# tracker.net
KiCad netlist of a schematic drawn in EAGLE
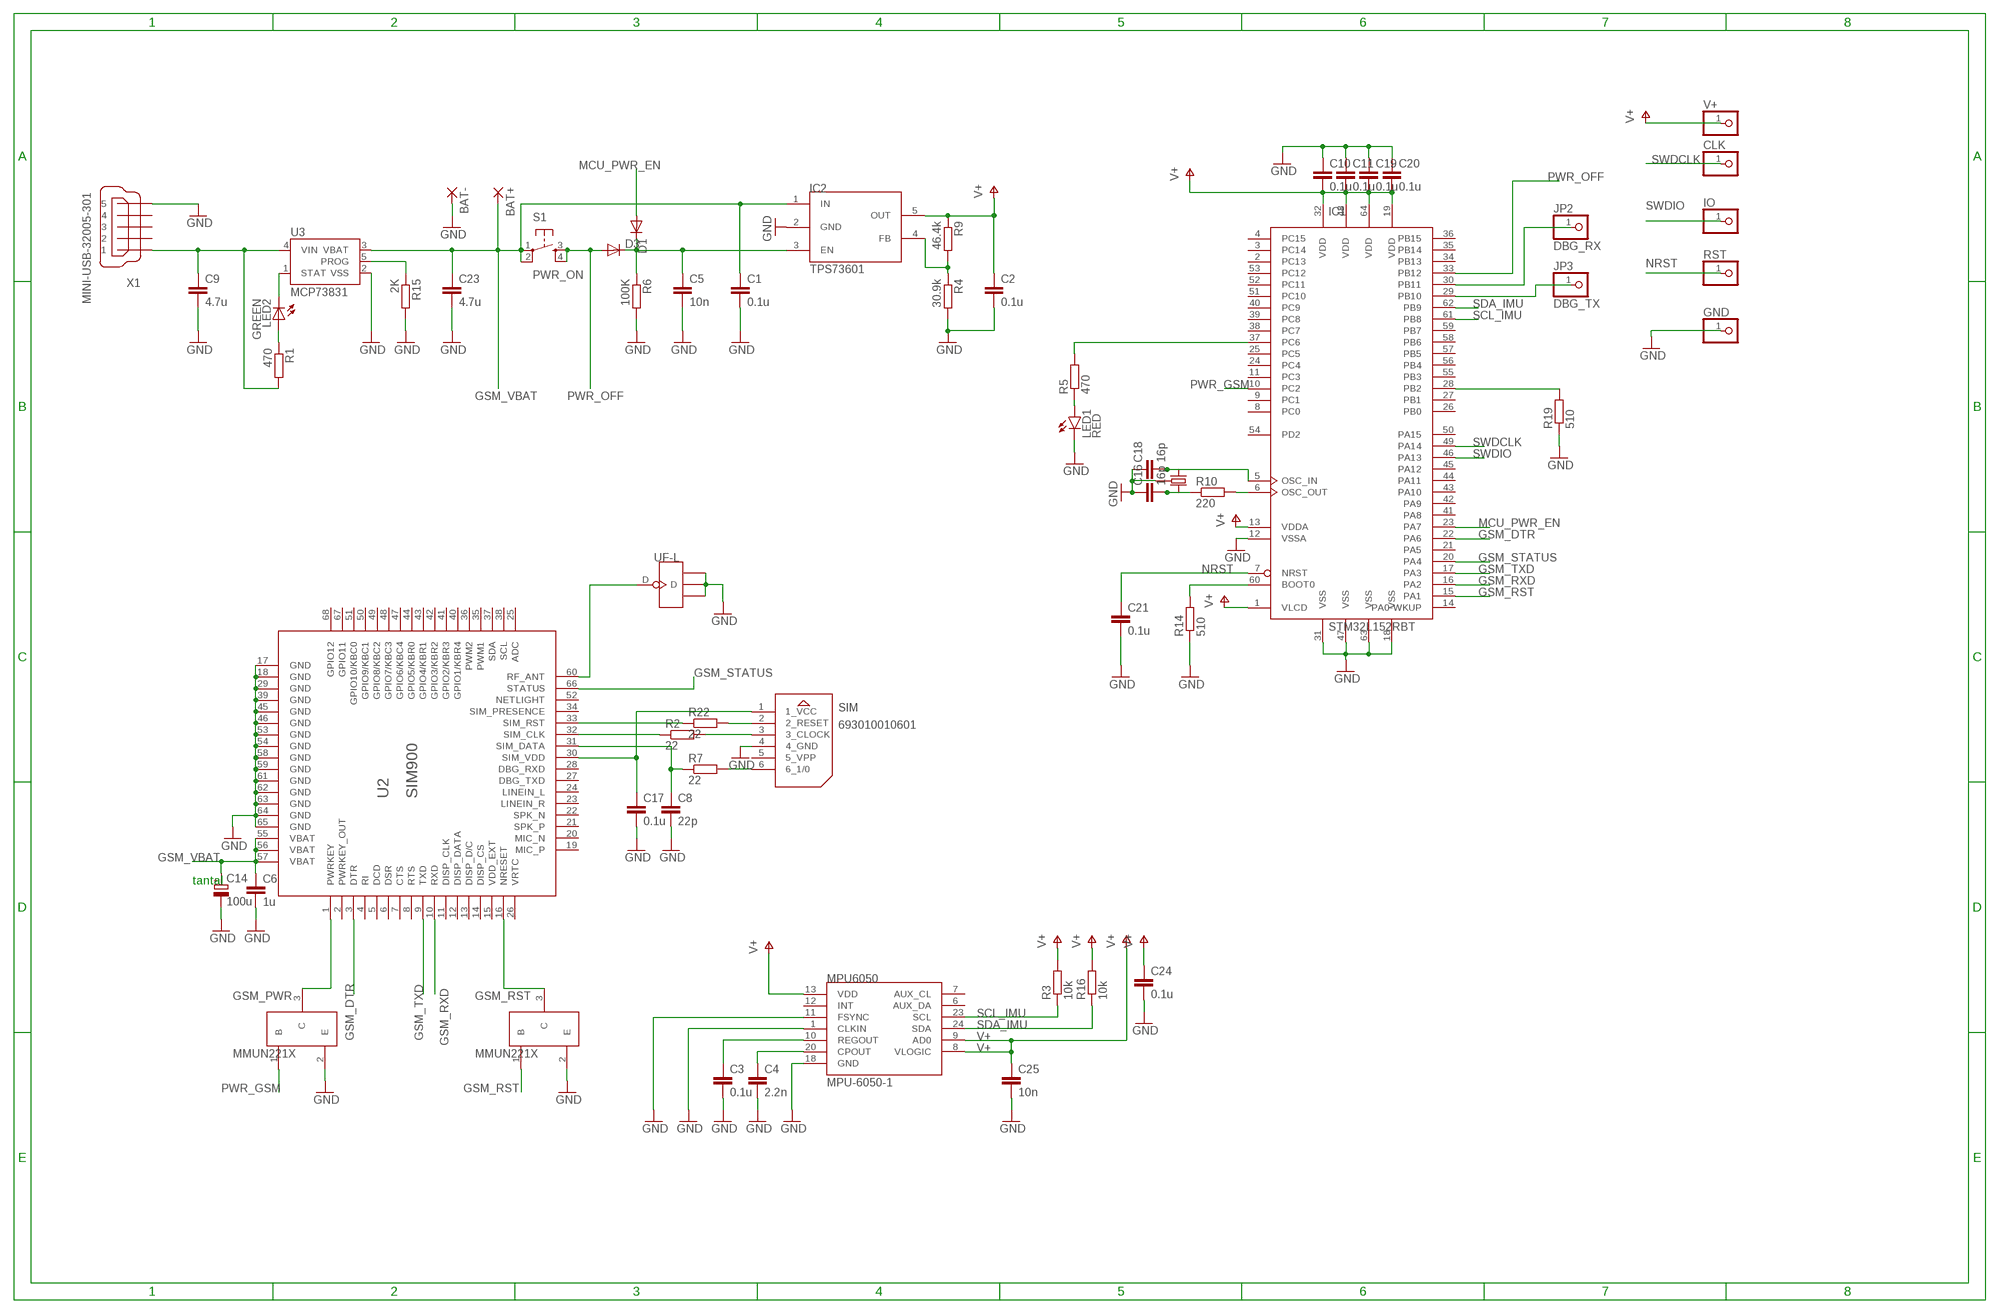
[diagram p0: schematic, sheet 1]

(export (version "E")
  (design (tool "Eeschema 10.0.6"))
  (components
    (comp (ref "BAT+")
      (value "SMD2")
      (footprint "eagle-import:SMD1,27-2,54")
      (libsource (lib "eagle-import") (part "SMD2"))
    )
    (comp (ref "BAT-")
      (value "SMD2")
      (footprint "eagle-import:SMD1,27-2,54")
      (libsource (lib "eagle-import") (part "SMD2"))
    )
    (comp (ref "C1")
      (value "0.1u")
      (footprint "eagle-import:C0805")
      (libsource (lib "eagle-import") (part "C-EUC0805"))
    )
    (comp (ref "C2")
      (value "0.1u")
      (footprint "eagle-import:C0805")
      (libsource (lib "eagle-import") (part "C-EUC0805"))
    )
    (comp (ref "C3")
      (value "0.1u")
      (footprint "eagle-import:C0805")
      (libsource (lib "eagle-import") (part "C-EUC0805"))
    )
    (comp (ref "C4")
      (value "2.2n")
      (footprint "eagle-import:C0805")
      (libsource (lib "eagle-import") (part "C-EUC0805"))
    )
    (comp (ref "C5")
      (value "10n")
      (footprint "eagle-import:C0805")
      (libsource (lib "eagle-import") (part "C-EUC0805"))
    )
    (comp (ref "C6")
      (value "1u")
      (footprint "eagle-import:C0805")
      (libsource (lib "eagle-import") (part "C-EUC0805"))
    )
    (comp (ref "C8")
      (value "22p")
      (footprint "eagle-import:C0805")
      (libsource (lib "eagle-import") (part "C-EUC0805"))
    )
    (comp (ref "C9")
      (value "4.7u")
      (footprint "eagle-import:C0805")
      (libsource (lib "eagle-import") (part "C-EUC0805"))
    )
    (comp (ref "C10")
      (value "0.1u")
      (footprint "eagle-import:C0805")
      (libsource (lib "eagle-import") (part "C-EUC0805"))
    )
    (comp (ref "C11")
      (value "0.1u")
      (footprint "eagle-import:C0805")
      (libsource (lib "eagle-import") (part "C-EUC0805"))
    )
    (comp (ref "C14")
      (value "100u")
      (footprint "eagle-import:C_6032-28R")
      (libsource (lib "eagle-import") (part "CPOL-EUC/6032-28R"))
    )
    (comp (ref "C16")
      (value "16p")
      (footprint "eagle-import:C0603")
      (libsource (lib "eagle-import") (part "C-EUC0603"))
    )
    (comp (ref "C17")
      (value "0.1u")
      (footprint "eagle-import:C0805")
      (libsource (lib "eagle-import") (part "C-EUC0805"))
    )
    (comp (ref "C18")
      (value "16p")
      (footprint "eagle-import:C0603")
      (libsource (lib "eagle-import") (part "C-EUC0603"))
    )
    (comp (ref "C19")
      (value "0.1u")
      (footprint "eagle-import:C0805")
      (libsource (lib "eagle-import") (part "C-EUC0805"))
    )
    (comp (ref "C20")
      (value "0.1u")
      (footprint "eagle-import:C0805")
      (libsource (lib "eagle-import") (part "C-EUC0805"))
    )
    (comp (ref "C21")
      (value "0.1u")
      (footprint "eagle-import:C0805")
      (libsource (lib "eagle-import") (part "C-EUC0805"))
    )
    (comp (ref "C23")
      (value "4.7u")
      (footprint "eagle-import:C0805")
      (libsource (lib "eagle-import") (part "C-EUC0805"))
    )
    (comp (ref "C24")
      (value "0.1u")
      (footprint "eagle-import:C0805")
      (libsource (lib "eagle-import") (part "C-EUC0805"))
    )
    (comp (ref "C25")
      (value "10n")
      (footprint "eagle-import:C0805")
      (libsource (lib "eagle-import") (part "C-EUC0805"))
    )
    (comp (ref "CLK")
      (value "PINHD-1X1")
      (footprint "eagle-import:1X01")
      (libsource (lib "eagle-import") (part "PINHD-1X1"))
    )
    (comp (ref "CRTL")
      (value "CRYSTAL-GROUNDED")
      (footprint "eagle-import:CRYSTAL-SMD-5X3")
      (libsource (lib "eagle-import") (part "CRYSTAL-GROUNDED"))
    )
    (comp (ref "D1")
      (value "MBR0520LT")
      (footprint "eagle-import:SOD123")
      (libsource (lib "eagle-import") (part "MBR0520LT"))
    )
    (comp (ref "D3")
      (value "MBR0520LT")
      (footprint "eagle-import:SOD123")
      (libsource (lib "eagle-import") (part "MBR0520LT"))
    )
    (comp (ref "GND")
      (value "PINHD-1X1")
      (footprint "eagle-import:1X01")
      (libsource (lib "eagle-import") (part "PINHD-1X1"))
    )
    (comp (ref "GSM_PWR")
      (value "MMUN221X")
      (footprint "eagle-import:MMUN221X")
      (libsource (lib "eagle-import") (part "MMUN221X"))
    )
    (comp (ref "GSM_RST")
      (value "MMUN221X")
      (footprint "eagle-import:MMUN221X")
      (libsource (lib "eagle-import") (part "MMUN221X"))
    )
    (comp (ref "IC1")
      (value "STM32L152RBT")
      (footprint "eagle-import:LQFP64")
      (fields (field (name "OC_NEWARK") "unknown"))
      (libsource (lib "eagle-import") (part "STM32L152RTB"))
    )
    (comp (ref "IC2")
      (value "TPS73601")
      (footprint "eagle-import:SOT23")
      (libsource (lib "eagle-import") (part "TPS73601"))
    )
    (comp (ref "IO")
      (value "PINHD-1X1")
      (footprint "eagle-import:1X01")
      (libsource (lib "eagle-import") (part "PINHD-1X1"))
    )
    (comp (ref "JP2")
      (value "DBG_RX")
      (footprint "eagle-import:1X01")
      (libsource (lib "eagle-import") (part "PINHD-1X1"))
    )
    (comp (ref "JP3")
      (value "DBG_TX")
      (footprint "eagle-import:1X01")
      (libsource (lib "eagle-import") (part "PINHD-1X1"))
    )
    (comp (ref "LED1")
      (value "RED")
      (footprint "eagle-import:LED-0603")
      (libsource (lib "eagle-import") (part "LED-RED0603"))
    )
    (comp (ref "LED2")
      (value "GREEN")
      (footprint "eagle-import:LED-0603")
      (libsource (lib "eagle-import") (part "LED0603"))
    )
    (comp (ref "MPU6050")
      (value "MPU-6050-1")
      (footprint "eagle-import:QFN-24-4MM2")
      (libsource (lib "eagle-import") (part "MPU-6050-1"))
    )
    (comp (ref "R1")
      (value "470")
      (footprint "eagle-import:R0805")
      (libsource (lib "eagle-import") (part "R-EU_R0805"))
    )
    (comp (ref "R2")
      (value "22")
      (footprint "eagle-import:R0805")
      (libsource (lib "eagle-import") (part "R-EU_R0805"))
    )
    (comp (ref "R3")
      (value "10k")
      (footprint "eagle-import:R0805")
      (libsource (lib "eagle-import") (part "R-EU_R0805"))
    )
    (comp (ref "R4")
      (value "30.9k")
      (footprint "eagle-import:R0805")
      (libsource (lib "eagle-import") (part "R-EU_R0805"))
    )
    (comp (ref "R5")
      (value "470")
      (footprint "eagle-import:R0805")
      (libsource (lib "eagle-import") (part "R-EU_R0805"))
    )
    (comp (ref "R6")
      (value "100K")
      (footprint "eagle-import:R0805")
      (libsource (lib "eagle-import") (part "R-EU_R0805"))
    )
    (comp (ref "R7")
      (value "22")
      (footprint "eagle-import:R0805")
      (libsource (lib "eagle-import") (part "R-EU_R0805"))
    )
    (comp (ref "R9")
      (value "46.4k")
      (footprint "eagle-import:R0805")
      (libsource (lib "eagle-import") (part "R-EU_R0805"))
    )
    (comp (ref "R10")
      (value "220")
      (footprint "eagle-import:R0805")
      (libsource (lib "eagle-import") (part "R-EU_R0805"))
    )
    (comp (ref "R14")
      (value "510")
      (footprint "eagle-import:R0805")
      (libsource (lib "eagle-import") (part "R-EU_R0805"))
    )
    (comp (ref "R15")
      (value "2K")
      (footprint "eagle-import:R0805")
      (libsource (lib "eagle-import") (part "R-EU_R0805"))
    )
    (comp (ref "R16")
      (value "10k")
      (footprint "eagle-import:R0805")
      (libsource (lib "eagle-import") (part "R-EU_R0805"))
    )
    (comp (ref "R19")
      (value "510")
      (footprint "eagle-import:R0805")
      (libsource (lib "eagle-import") (part "R-EU_R0805"))
    )
    (comp (ref "R22")
      (value "22")
      (footprint "eagle-import:R0805")
      (libsource (lib "eagle-import") (part "R-EU_R0805"))
    )
    (comp (ref "RST")
      (value "PINHD-1X1")
      (footprint "eagle-import:1X01")
      (libsource (lib "eagle-import") (part "PINHD-1X1"))
    )
    (comp (ref "S1")
      (value "PWR_ON")
      (footprint "eagle-import:TACTILE-PTH")
      (libsource (lib "eagle-import") (part "TAC_SWITCHPTH"))
    )
    (comp (ref "SIM")
      (value "693010010601")
      (footprint "eagle-import:693010010601")
      (libsource (lib "eagle-import") (part "693010010601"))
    )
    (comp (ref "U2")
      (value "SIM900")
      (footprint "eagle-import:SIM900")
      (libsource (lib "eagle-import") (part "SIM900"))
    )
    (comp (ref "U3")
      (value "MCP73831")
      (footprint "eagle-import:SOT23-5")
      (libsource (lib "eagle-import") (part "MCP73831"))
    )
    (comp (ref "UF-L")
      (value "ANTENNA-U-FL")
      (footprint "eagle-import:4P-U-FL")
      (libsource (lib "eagle-import") (part "ANTENNA-U-FL"))
    )
    (comp (ref "V+")
      (value "PINHD-1X1")
      (footprint "eagle-import:1X01")
      (libsource (lib "eagle-import") (part "PINHD-1X1"))
    )
    (comp (ref "X1")
      (value "MINI-USB-32005-301")
      (footprint "eagle-import:32005-301")
      (libsource (lib "eagle-import") (part "MINI-USB-32005-301"))
    )
  )
  (nets
    (net (code "1") (name "/GSM_DTR") (class "Default")
      (node (ref "IC1") (pin "22") (pinfunction "PA6_22") (pintype "bidirectional"))
      (node (ref "U2") (pin "3") (pinfunction "DTR_3") (pintype "input"))
    )
    (net (code "2") (name "/GSM_RST") (class "Default")
      (node (ref "GSM_RST") (pin "1") (pinfunction "B_1") (pintype "bidirectional"))
      (node (ref "IC1") (pin "15") (pinfunction "PA1_15") (pintype "bidirectional"))
    )
    (net (code "3") (name "/GSM_RXD") (class "Default")
      (node (ref "IC1") (pin "16") (pinfunction "PA2_16") (pintype "bidirectional"))
      (node (ref "U2") (pin "10") (pinfunction "RXD_10") (pintype "input"))
    )
    (net (code "4") (name "/GSM_STATUS") (class "Default")
      (node (ref "IC1") (pin "20") (pinfunction "PA4_20") (pintype "bidirectional"))
      (node (ref "U2") (pin "66") (pinfunction "STATUS_66") (pintype "output"))
    )
    (net (code "5") (name "/GSM_TXD") (class "Default")
      (node (ref "IC1") (pin "17") (pinfunction "PA3_17") (pintype "bidirectional"))
      (node (ref "U2") (pin "9") (pinfunction "TXD_9") (pintype "output"))
    )
    (net (code "6") (name "/GSM_VBAT") (class "Default")
      (node (ref "BAT+") (pin "1") (pinfunction "P_1") (pintype "passive"))
      (node (ref "C1") (pin "1") (pinfunction "1_1") (pintype "passive"))
      (node (ref "C14") (pin "+") (pinfunction "+_+") (pintype "passive"))
      (node (ref "C23") (pin "1") (pinfunction "1_1") (pintype "passive"))
      (node (ref "C6") (pin "1") (pinfunction "1_1") (pintype "passive"))
      (node (ref "IC2") (pin "1") (pinfunction "IN_1") (pintype "power_in"))
      (node (ref "S1") (pin "1") (pinfunction "1_1") (pintype "passive"))
      (node (ref "S1") (pin "2") (pinfunction "2_2") (pintype "passive"))
      (node (ref "U2") (pin "55") (pinfunction "VBAT_55") (pintype "power_in"))
      (node (ref "U2") (pin "56") (pinfunction "VBAT_56") (pintype "power_in"))
      (node (ref "U2") (pin "57") (pinfunction "VBAT_57") (pintype "power_in"))
      (node (ref "U3") (pin "3") (pinfunction "VBAT_3") (pintype "power_in"))
    )
    (net (code "7") (name "/MCU_PWR_EN") (class "Default")
      (node (ref "D1") (pin "A") (pinfunction "A_A") (pintype "passive"))
      (node (ref "IC1") (pin "23") (pinfunction "PA7_23") (pintype "bidirectional"))
    )
    (net (code "8") (name "/NRST") (class "Default")
      (node (ref "C21") (pin "1") (pinfunction "1_1") (pintype "passive"))
      (node (ref "IC1") (pin "7") (pinfunction "NRST_7") (pintype "bidirectional"))
      (node (ref "RST") (pin "1") (pinfunction "1_1") (pintype "passive"))
    )
    (net (code "9") (name "/PWR_GSM") (class "Default")
      (node (ref "GSM_PWR") (pin "1") (pinfunction "B_1") (pintype "bidirectional"))
      (node (ref "IC1") (pin "10") (pinfunction "PC2_10") (pintype "bidirectional"))
    )
    (net (code "10") (name "/PWR_OFF") (class "Default")
      (node (ref "D3") (pin "A") (pinfunction "A_A") (pintype "passive"))
      (node (ref "IC1") (pin "33") (pinfunction "PB12_33") (pintype "bidirectional"))
      (node (ref "S1") (pin "3") (pinfunction "3_3") (pintype "passive"))
      (node (ref "S1") (pin "4") (pinfunction "4_4") (pintype "passive"))
    )
    (net (code "11") (name "/SCL_IMU") (class "Default")
      (node (ref "IC1") (pin "61") (pinfunction "PB8_61") (pintype "bidirectional"))
      (node (ref "MPU6050") (pin "23") (pinfunction "SCL_23") (pintype "bidirectional"))
      (node (ref "R3") (pin "1") (pinfunction "1_1") (pintype "passive"))
    )
    (net (code "12") (name "/SDA_IMU") (class "Default")
      (node (ref "IC1") (pin "62") (pinfunction "PB9_62") (pintype "bidirectional"))
      (node (ref "MPU6050") (pin "24") (pinfunction "SDA_24") (pintype "bidirectional"))
      (node (ref "R16") (pin "1") (pinfunction "1_1") (pintype "passive"))
    )
    (net (code "13") (name "/SWDCLK") (class "Default")
      (node (ref "CLK") (pin "1") (pinfunction "1_1") (pintype "passive"))
      (node (ref "IC1") (pin "49") (pinfunction "PA14_49") (pintype "bidirectional"))
    )
    (net (code "14") (name "/SWDIO") (class "Default")
      (node (ref "IC1") (pin "46") (pinfunction "PA13_46") (pintype "bidirectional"))
      (node (ref "IO") (pin "1") (pinfunction "1_1") (pintype "passive"))
    )
    (net (code "15") (name "GND") (class "Default")
      (node (ref "BAT-") (pin "1") (pinfunction "P_1") (pintype "passive"))
      (node (ref "C1") (pin "2") (pinfunction "2_2") (pintype "passive"))
      (node (ref "C10") (pin "1") (pinfunction "1_1") (pintype "passive"))
      (node (ref "C11") (pin "1") (pinfunction "1_1") (pintype "passive"))
      (node (ref "C14") (pin "-") (pinfunction "-_-") (pintype "passive"))
      (node (ref "C16") (pin "1") (pinfunction "1_1") (pintype "passive"))
      (node (ref "C17") (pin "2") (pinfunction "2_2") (pintype "passive"))
      (node (ref "C18") (pin "1") (pinfunction "1_1") (pintype "passive"))
      (node (ref "C19") (pin "1") (pinfunction "1_1") (pintype "passive"))
      (node (ref "C2") (pin "2") (pinfunction "2_2") (pintype "passive"))
      (node (ref "C20") (pin "1") (pinfunction "1_1") (pintype "passive"))
      (node (ref "C21") (pin "2") (pinfunction "2_2") (pintype "passive"))
      (node (ref "C23") (pin "2") (pinfunction "2_2") (pintype "passive"))
      (node (ref "C24") (pin "2") (pinfunction "2_2") (pintype "passive"))
      (node (ref "C25") (pin "2") (pinfunction "2_2") (pintype "passive"))
      (node (ref "C3") (pin "2") (pinfunction "2_2") (pintype "passive"))
      (node (ref "C4") (pin "2") (pinfunction "2_2") (pintype "passive"))
      (node (ref "C5") (pin "2") (pinfunction "2_2") (pintype "passive"))
      (node (ref "C6") (pin "2") (pinfunction "2_2") (pintype "passive"))
      (node (ref "C8") (pin "2") (pinfunction "2_2") (pintype "passive"))
      (node (ref "C9") (pin "2") (pinfunction "2_2") (pintype "passive"))
      (node (ref "CRTL") (pin "2") (pinfunction "3_2") (pintype "passive"))
      (node (ref "CRTL") (pin "4") (pinfunction "3_4") (pintype "passive"))
      (node (ref "GND") (pin "1") (pinfunction "1_1") (pintype "passive"))
      (node (ref "GSM_PWR") (pin "2") (pinfunction "E_2") (pintype "bidirectional"))
      (node (ref "GSM_RST") (pin "2") (pinfunction "E_2") (pintype "bidirectional"))
      (node (ref "IC1") (pin "12") (pinfunction "VSSA_12") (pintype "power_in"))
      (node (ref "IC1") (pin "18") (pinfunction "VSS_18") (pintype "power_in"))
      (node (ref "IC1") (pin "31") (pinfunction "VSS_31") (pintype "power_in"))
      (node (ref "IC1") (pin "47") (pinfunction "VSS_47") (pintype "power_in"))
      (node (ref "IC1") (pin "63") (pinfunction "VSS_63") (pintype "power_in"))
      (node (ref "IC2") (pin "2") (pinfunction "GND_2") (pintype "power_in"))
      (node (ref "LED1") (pin "C") (pinfunction "C_C") (pintype "passive"))
      (node (ref "MPU6050") (pin "1") (pinfunction "CLKIN_1") (pintype "bidirectional"))
      (node (ref "MPU6050") (pin "11") (pinfunction "FSYNC_11") (pintype "bidirectional"))
      (node (ref "MPU6050") (pin "18") (pinfunction "GND_18") (pintype "bidirectional"))
      (node (ref "R14") (pin "1") (pinfunction "1_1") (pintype "passive"))
      (node (ref "R15") (pin "2") (pinfunction "2_2") (pintype "passive"))
      (node (ref "R19") (pin "1") (pinfunction "1_1") (pintype "passive"))
      (node (ref "R4") (pin "2") (pinfunction "2_2") (pintype "passive"))
      (node (ref "R6") (pin "2") (pinfunction "2_2") (pintype "passive"))
      (node (ref "SIM") (pin "4") (pinfunction "4_GND_4") (pintype "bidirectional"))
      (node (ref "U2") (pin "17") (pinfunction "GND_17") (pintype "power_in"))
      (node (ref "U2") (pin "18") (pinfunction "GND_18") (pintype "power_in"))
      (node (ref "U2") (pin "29") (pinfunction "GND_29") (pintype "power_in"))
      (node (ref "U2") (pin "39") (pinfunction "GND_39") (pintype "power_in"))
      (node (ref "U2") (pin "45") (pinfunction "GND_45") (pintype "power_in"))
      (node (ref "U2") (pin "46") (pinfunction "GND_46") (pintype "power_in"))
      (node (ref "U2") (pin "53") (pinfunction "GND_53") (pintype "power_in"))
      (node (ref "U2") (pin "54") (pinfunction "GND_54") (pintype "power_in"))
      (node (ref "U2") (pin "58") (pinfunction "GND_58") (pintype "power_in"))
      (node (ref "U2") (pin "59") (pinfunction "GND_59") (pintype "power_in"))
      (node (ref "U2") (pin "61") (pinfunction "GND_61") (pintype "power_in"))
      (node (ref "U2") (pin "62") (pinfunction "GND_62") (pintype "power_in"))
      (node (ref "U2") (pin "63") (pinfunction "GND_63") (pintype "power_in"))
      (node (ref "U2") (pin "64") (pinfunction "GND_64") (pintype "power_in"))
      (node (ref "U2") (pin "65") (pinfunction "GND_65") (pintype "power_in"))
      (node (ref "U3") (pin "2") (pinfunction "VSS_2") (pintype "power_in"))
      (node (ref "UF-L") (pin "GND1") (pinfunction "GND1_GND1") (pintype "bidirectional"))
      (node (ref "UF-L") (pin "GND2") (pinfunction "GND2_GND2") (pintype "bidirectional"))
      (node (ref "UF-L") (pin "GND3") (pinfunction "GND3_GND3") (pintype "bidirectional"))
      (node (ref "X1") (pin "5") (pinfunction "5_5") (pintype "passive"))
    )
    (net (code "16") (name "Net-(CRTL-1)") (class "Default")
      (node (ref "C18") (pin "2") (pinfunction "2_2") (pintype "passive"))
      (node (ref "CRTL") (pin "3") (pinfunction "1_3") (pintype "passive"))
      (node (ref "IC1") (pin "5") (pinfunction "OSC_IN_5") (pintype "bidirectional"))
    )
    (net (code "17") (name "Net-(CRTL-2)") (class "Default")
      (node (ref "C16") (pin "2") (pinfunction "2_2") (pintype "passive"))
      (node (ref "CRTL") (pin "1") (pinfunction "2_1") (pintype "passive"))
      (node (ref "R10") (pin "1") (pinfunction "1_1") (pintype "passive"))
    )
    (net (code "18") (name "Net-(GSM_PWR-C)") (class "Default")
      (node (ref "GSM_PWR") (pin "3") (pinfunction "C_3") (pintype "bidirectional"))
      (node (ref "U2") (pin "1") (pinfunction "PWRKEY_1") (pintype "input"))
    )
    (net (code "19") (name "Net-(GSM_RST-C)") (class "Default")
      (node (ref "GSM_RST") (pin "3") (pinfunction "C_3") (pintype "bidirectional"))
      (node (ref "U2") (pin "16") (pinfunction "NRESET_16") (pintype "input"))
    )
    (net (code "20") (name "Net-(IC1A-BOOT0)") (class "Default")
      (node (ref "IC1") (pin "60") (pinfunction "BOOT0_60") (pintype "input"))
      (node (ref "R14") (pin "2") (pinfunction "2_2") (pintype "passive"))
    )
    (net (code "21") (name "Net-(IC1A-OSC_OUT)") (class "Default")
      (node (ref "IC1") (pin "6") (pinfunction "OSC_OUT_6") (pintype "bidirectional"))
      (node (ref "R10") (pin "2") (pinfunction "2_2") (pintype "passive"))
    )
    (net (code "22") (name "Net-(IC1A-PB2)") (class "Default")
      (node (ref "IC1") (pin "28") (pinfunction "PB2_28") (pintype "bidirectional"))
      (node (ref "R19") (pin "2") (pinfunction "2_2") (pintype "passive"))
    )
    (net (code "23") (name "Net-(IC1A-PB10)") (class "Default")
      (node (ref "IC1") (pin "29") (pinfunction "PB10_29") (pintype "bidirectional"))
      (node (ref "JP3") (pin "1") (pinfunction "1_1") (pintype "passive"))
    )
    (net (code "24") (name "Net-(IC1A-PB11)") (class "Default")
      (node (ref "IC1") (pin "30") (pinfunction "PB11_30") (pintype "bidirectional"))
      (node (ref "JP2") (pin "1") (pinfunction "1_1") (pintype "passive"))
    )
    (net (code "25") (name "Net-(IC1A-PC6)") (class "Default")
      (node (ref "IC1") (pin "37") (pinfunction "PC6_37") (pintype "bidirectional"))
      (node (ref "R5") (pin "2") (pinfunction "2_2") (pintype "passive"))
    )
    (net (code "26") (name "Net-(IC2-EN)") (class "Default")
      (node (ref "C5") (pin "1") (pinfunction "1_1") (pintype "passive"))
      (node (ref "D1") (pin "C") (pinfunction "C_C") (pintype "passive"))
      (node (ref "D3") (pin "C") (pinfunction "C_C") (pintype "passive"))
      (node (ref "IC2") (pin "3") (pinfunction "EN_3") (pintype "passive"))
      (node (ref "R6") (pin "1") (pinfunction "1_1") (pintype "passive"))
    )
    (net (code "27") (name "Net-(IC2-FB)") (class "Default")
      (node (ref "IC2") (pin "4") (pinfunction "FB_4") (pintype "power_in"))
      (node (ref "R4") (pin "1") (pinfunction "1_1") (pintype "passive"))
      (node (ref "R9") (pin "2") (pinfunction "2_2") (pintype "passive"))
    )
    (net (code "28") (name "Net-(LED1-PadA)") (class "Default")
      (node (ref "LED1") (pin "A") (pinfunction "A_A") (pintype "passive"))
      (node (ref "R5") (pin "1") (pinfunction "1_1") (pintype "passive"))
    )
    (net (code "29") (name "Net-(LED2-PadA)") (class "Default")
      (node (ref "LED2") (pin "A") (pinfunction "A_A") (pintype "passive"))
      (node (ref "R1") (pin "1") (pinfunction "1_1") (pintype "passive"))
    )
    (net (code "30") (name "Net-(MPU6050-CPOUT)") (class "Default")
      (node (ref "C4") (pin "1") (pinfunction "1_1") (pintype "passive"))
      (node (ref "MPU6050") (pin "20") (pinfunction "CPOUT_20") (pintype "bidirectional"))
    )
    (net (code "31") (name "Net-(MPU6050-REGOUT)") (class "Default")
      (node (ref "C3") (pin "1") (pinfunction "1_1") (pintype "passive"))
      (node (ref "MPU6050") (pin "10") (pinfunction "REGOUT_10") (pintype "bidirectional"))
    )
    (net (code "32") (name "Net-(SIM-1_VCC)") (class "Default")
      (node (ref "C17") (pin "1") (pinfunction "1_1") (pintype "passive"))
      (node (ref "SIM") (pin "1") (pinfunction "1_VCC_1") (pintype "bidirectional"))
      (node (ref "U2") (pin "30") (pinfunction "SIM_VDD_30") (pintype "output"))
    )
    (net (code "33") (name "Net-(SIM-2_RESET)") (class "Default")
      (node (ref "R22") (pin "2") (pinfunction "2_2") (pintype "passive"))
      (node (ref "SIM") (pin "2") (pinfunction "2_RESET_2") (pintype "bidirectional"))
    )
    (net (code "34") (name "Net-(SIM-3_CLOCK)") (class "Default")
      (node (ref "R2") (pin "2") (pinfunction "2_2") (pintype "passive"))
      (node (ref "SIM") (pin "3") (pinfunction "3_CLOCK_3") (pintype "bidirectional"))
    )
    (net (code "35") (name "Net-(SIM-6_1{slash}0)") (class "Default")
      (node (ref "R7") (pin "2") (pinfunction "2_2") (pintype "passive"))
      (node (ref "SIM") (pin "6") (pinfunction "6_1/0_6") (pintype "bidirectional"))
    )
    (net (code "36") (name "Net-(U2-RF_ANT)") (class "Default")
      (node (ref "U2") (pin "60") (pinfunction "RF_ANT_60") (pintype "bidirectional"))
      (node (ref "UF-L") (pin "D") (pinfunction "D_D") (pintype "bidirectional"))
    )
    (net (code "37") (name "Net-(U2-SIM_CLK)") (class "Default")
      (node (ref "R2") (pin "1") (pinfunction "1_1") (pintype "passive"))
      (node (ref "U2") (pin "32") (pinfunction "SIM_CLK_32") (pintype "output"))
    )
    (net (code "38") (name "Net-(U2-SIM_DATA)") (class "Default")
      (node (ref "C8") (pin "1") (pinfunction "1_1") (pintype "passive"))
      (node (ref "R7") (pin "1") (pinfunction "1_1") (pintype "passive"))
      (node (ref "U2") (pin "31") (pinfunction "SIM_DATA_31") (pintype "bidirectional"))
    )
    (net (code "39") (name "Net-(U2-SIM_RST)") (class "Default")
      (node (ref "R22") (pin "1") (pinfunction "1_1") (pintype "passive"))
      (node (ref "U2") (pin "33") (pinfunction "SIM_RST_33") (pintype "output"))
    )
    (net (code "40") (name "Net-(U3-PROG)") (class "Default")
      (node (ref "R15") (pin "1") (pinfunction "1_1") (pintype "passive"))
      (node (ref "U3") (pin "5") (pinfunction "PROG_5") (pintype "input"))
    )
    (net (code "41") (name "Net-(U3-STAT)") (class "Default")
      (node (ref "LED2") (pin "C") (pinfunction "C_C") (pintype "passive"))
      (node (ref "U3") (pin "1") (pinfunction "STAT_1") (pintype "output"))
    )
    (net (code "42") (name "Net-(U3-VIN)") (class "Default")
      (node (ref "C9") (pin "1") (pinfunction "1_1") (pintype "passive"))
      (node (ref "R1") (pin "2") (pinfunction "2_2") (pintype "passive"))
      (node (ref "U3") (pin "4") (pinfunction "VIN_4") (pintype "power_in"))
      (node (ref "X1") (pin "1") (pinfunction "1_1") (pintype "passive"))
    )
    (net (code "43") (name "V+") (class "Default")
      (node (ref "C10") (pin "2") (pinfunction "2_2") (pintype "passive"))
      (node (ref "C11") (pin "2") (pinfunction "2_2") (pintype "passive"))
      (node (ref "C19") (pin "2") (pinfunction "2_2") (pintype "passive"))
      (node (ref "C2") (pin "1") (pinfunction "1_1") (pintype "passive"))
      (node (ref "C20") (pin "2") (pinfunction "2_2") (pintype "passive"))
      (node (ref "C24") (pin "1") (pinfunction "1_1") (pintype "passive"))
      (node (ref "C25") (pin "1") (pinfunction "1_1") (pintype "passive"))
      (node (ref "IC1") (pin "1") (pinfunction "VLCD_1") (pintype "power_in"))
      (node (ref "IC1") (pin "13") (pinfunction "VDDA_13") (pintype "power_in"))
      (node (ref "IC1") (pin "19") (pinfunction "VDD_19") (pintype "power_in"))
      (node (ref "IC1") (pin "32") (pinfunction "VDD_32") (pintype "power_in"))
      (node (ref "IC1") (pin "48") (pinfunction "VDD_48") (pintype "power_in"))
      (node (ref "IC1") (pin "64") (pinfunction "VDD_64") (pintype "power_in"))
      (node (ref "IC2") (pin "5") (pinfunction "OUT_5") (pintype "power_in"))
      (node (ref "MPU6050") (pin "13") (pinfunction "VDD_13") (pintype "bidirectional"))
      (node (ref "MPU6050") (pin "8") (pinfunction "VLOGIC_8") (pintype "bidirectional"))
      (node (ref "MPU6050") (pin "9") (pinfunction "AD0_9") (pintype "bidirectional"))
      (node (ref "R16") (pin "2") (pinfunction "2_2") (pintype "passive"))
      (node (ref "R3") (pin "2") (pinfunction "2_2") (pintype "passive"))
      (node (ref "R9") (pin "1") (pinfunction "1_1") (pintype "passive"))
      (node (ref "V+") (pin "1") (pinfunction "1_1") (pintype "passive"))
    )
    (net (code "44") (name "unconnected-(IC1A-PA0-WKUP-Pad14)") (class "Default")
      (node (ref "IC1") (pin "14") (pinfunction "PA0-WKUP_14") (pintype "bidirectional"))
    )
    (net (code "45") (name "unconnected-(IC1A-PA5-Pad21)") (class "Default")
      (node (ref "IC1") (pin "21") (pinfunction "PA5_21") (pintype "bidirectional"))
    )
    (net (code "46") (name "unconnected-(IC1A-PA8-Pad41)") (class "Default")
      (node (ref "IC1") (pin "41") (pinfunction "PA8_41") (pintype "bidirectional"))
    )
    (net (code "47") (name "unconnected-(IC1A-PA9-Pad42)") (class "Default")
      (node (ref "IC1") (pin "42") (pinfunction "PA9_42") (pintype "bidirectional"))
    )
    (net (code "48") (name "unconnected-(IC1A-PA10-Pad43)") (class "Default")
      (node (ref "IC1") (pin "43") (pinfunction "PA10_43") (pintype "bidirectional"))
    )
    (net (code "49") (name "unconnected-(IC1A-PA11-Pad44)") (class "Default")
      (node (ref "IC1") (pin "44") (pinfunction "PA11_44") (pintype "bidirectional"))
    )
    (net (code "50") (name "unconnected-(IC1A-PA12-Pad45)") (class "Default")
      (node (ref "IC1") (pin "45") (pinfunction "PA12_45") (pintype "bidirectional"))
    )
    (net (code "51") (name "unconnected-(IC1A-PA15-Pad50)") (class "Default")
      (node (ref "IC1") (pin "50") (pinfunction "PA15_50") (pintype "bidirectional"))
    )
    (net (code "52") (name "unconnected-(IC1A-PB0-Pad26)") (class "Default")
      (node (ref "IC1") (pin "26") (pinfunction "PB0_26") (pintype "bidirectional"))
    )
    (net (code "53") (name "unconnected-(IC1A-PB1-Pad27)") (class "Default")
      (node (ref "IC1") (pin "27") (pinfunction "PB1_27") (pintype "bidirectional"))
    )
    (net (code "54") (name "unconnected-(IC1A-PB3-Pad55)") (class "Default")
      (node (ref "IC1") (pin "55") (pinfunction "PB3_55") (pintype "bidirectional"))
    )
    (net (code "55") (name "unconnected-(IC1A-PB4-Pad56)") (class "Default")
      (node (ref "IC1") (pin "56") (pinfunction "PB4_56") (pintype "bidirectional"))
    )
    (net (code "56") (name "unconnected-(IC1A-PB5-Pad57)") (class "Default")
      (node (ref "IC1") (pin "57") (pinfunction "PB5_57") (pintype "bidirectional"))
    )
    (net (code "57") (name "unconnected-(IC1A-PB6-Pad58)") (class "Default")
      (node (ref "IC1") (pin "58") (pinfunction "PB6_58") (pintype "bidirectional"))
    )
    (net (code "58") (name "unconnected-(IC1A-PB7-Pad59)") (class "Default")
      (node (ref "IC1") (pin "59") (pinfunction "PB7_59") (pintype "bidirectional"))
    )
    (net (code "59") (name "unconnected-(IC1A-PB13-Pad34)") (class "Default")
      (node (ref "IC1") (pin "34") (pinfunction "PB13_34") (pintype "bidirectional"))
    )
    (net (code "60") (name "unconnected-(IC1A-PB14-Pad35)") (class "Default")
      (node (ref "IC1") (pin "35") (pinfunction "PB14_35") (pintype "bidirectional"))
    )
    (net (code "61") (name "unconnected-(IC1A-PB15-Pad36)") (class "Default")
      (node (ref "IC1") (pin "36") (pinfunction "PB15_36") (pintype "bidirectional"))
    )
    (net (code "62") (name "unconnected-(IC1A-PC0-Pad8)") (class "Default")
      (node (ref "IC1") (pin "8") (pinfunction "PC0_8") (pintype "bidirectional"))
    )
    (net (code "63") (name "unconnected-(IC1A-PC1-Pad9)") (class "Default")
      (node (ref "IC1") (pin "9") (pinfunction "PC1_9") (pintype "bidirectional"))
    )
    (net (code "64") (name "unconnected-(IC1A-PC3-Pad11)") (class "Default")
      (node (ref "IC1") (pin "11") (pinfunction "PC3_11") (pintype "bidirectional"))
    )
    (net (code "65") (name "unconnected-(IC1A-PC4-Pad24)") (class "Default")
      (node (ref "IC1") (pin "24") (pinfunction "PC4_24") (pintype "bidirectional"))
    )
    (net (code "66") (name "unconnected-(IC1A-PC5-Pad25)") (class "Default")
      (node (ref "IC1") (pin "25") (pinfunction "PC5_25") (pintype "bidirectional"))
    )
    (net (code "67") (name "unconnected-(IC1A-PC7-Pad38)") (class "Default")
      (node (ref "IC1") (pin "38") (pinfunction "PC7_38") (pintype "bidirectional"))
    )
    (net (code "68") (name "unconnected-(IC1A-PC8-Pad39)") (class "Default")
      (node (ref "IC1") (pin "39") (pinfunction "PC8_39") (pintype "bidirectional"))
    )
    (net (code "69") (name "unconnected-(IC1A-PC9-Pad40)") (class "Default")
      (node (ref "IC1") (pin "40") (pinfunction "PC9_40") (pintype "bidirectional"))
    )
    (net (code "70") (name "unconnected-(IC1A-PC10-Pad51)") (class "Default")
      (node (ref "IC1") (pin "51") (pinfunction "PC10_51") (pintype "bidirectional"))
    )
    (net (code "71") (name "unconnected-(IC1A-PC11-Pad52)") (class "Default")
      (node (ref "IC1") (pin "52") (pinfunction "PC11_52") (pintype "bidirectional"))
    )
    (net (code "72") (name "unconnected-(IC1A-PC12-Pad53)") (class "Default")
      (node (ref "IC1") (pin "53") (pinfunction "PC12_53") (pintype "bidirectional"))
    )
    (net (code "73") (name "unconnected-(IC1A-PC13-Pad2)") (class "Default")
      (node (ref "IC1") (pin "2") (pinfunction "PC13_2") (pintype "bidirectional"))
    )
    (net (code "74") (name "unconnected-(IC1A-PC14-Pad3)") (class "Default")
      (node (ref "IC1") (pin "3") (pinfunction "PC14_3") (pintype "bidirectional"))
    )
    (net (code "75") (name "unconnected-(IC1A-PC15-Pad4)") (class "Default")
      (node (ref "IC1") (pin "4") (pinfunction "PC15_4") (pintype "bidirectional"))
    )
    (net (code "76") (name "unconnected-(IC1A-PD2-Pad54)") (class "Default")
      (node (ref "IC1") (pin "54") (pinfunction "PD2_54") (pintype "bidirectional"))
    )
    (net (code "77") (name "unconnected-(MPU6050-AUX_CL-Pad7)") (class "Default")
      (node (ref "MPU6050") (pin "7") (pinfunction "AUX_CL_7") (pintype "bidirectional"))
    )
    (net (code "78") (name "unconnected-(MPU6050-AUX_DA-Pad6)") (class "Default")
      (node (ref "MPU6050") (pin "6") (pinfunction "AUX_DA_6") (pintype "bidirectional"))
    )
    (net (code "79") (name "unconnected-(MPU6050-INT-Pad12)") (class "Default")
      (node (ref "MPU6050") (pin "12") (pinfunction "INT_12") (pintype "bidirectional"))
    )
    (net (code "80") (name "unconnected-(SIM-5_VPP-Pad5)") (class "Default")
      (node (ref "SIM") (pin "5") (pinfunction "5_VPP_5") (pintype "bidirectional"))
    )
    (net (code "81") (name "unconnected-(U2-ADC-Pad25)") (class "Default")
      (node (ref "U2") (pin "25") (pinfunction "ADC_25") (pintype "input"))
    )
    (net (code "82") (name "unconnected-(U2-CTS-Pad7)") (class "Default")
      (node (ref "U2") (pin "7") (pinfunction "CTS_7") (pintype "output"))
    )
    (net (code "83") (name "unconnected-(U2-DBG_RXD-Pad28)") (class "Default")
      (node (ref "U2") (pin "28") (pinfunction "DBG_RXD_28") (pintype "input"))
    )
    (net (code "84") (name "unconnected-(U2-DBG_TXD-Pad27)") (class "Default")
      (node (ref "U2") (pin "27") (pinfunction "DBG_TXD_27") (pintype "output"))
    )
    (net (code "85") (name "unconnected-(U2-DCD-Pad5)") (class "Default")
      (node (ref "U2") (pin "5") (pinfunction "DCD_5") (pintype "output"))
    )
    (net (code "86") (name "unconnected-(U2-DISP_CLK-Pad11)") (class "Default")
      (node (ref "U2") (pin "11") (pinfunction "DISP_CLK_11") (pintype "output"))
    )
    (net (code "87") (name "unconnected-(U2-DISP_CS-Pad14)") (class "Default")
      (node (ref "U2") (pin "14") (pinfunction "DISP_CS_14") (pintype "output"))
    )
    (net (code "88") (name "unconnected-(U2-DISP_DATA-Pad12)") (class "Default")
      (node (ref "U2") (pin "12") (pinfunction "DISP_DATA_12") (pintype "bidirectional"))
    )
    (net (code "89") (name "unconnected-(U2-DISP_D{slash}C-Pad13)") (class "Default")
      (node (ref "U2") (pin "13") (pinfunction "DISP_D/C_13") (pintype "output"))
    )
    (net (code "90") (name "unconnected-(U2-DSR-Pad6)") (class "Default")
      (node (ref "U2") (pin "6") (pinfunction "DSR_6") (pintype "output"))
    )
    (net (code "91") (name "unconnected-(U2-GPIO1{slash}KBR4-Pad40)") (class "Default")
      (node (ref "U2") (pin "40") (pinfunction "GPIO1/KBR4_40") (pintype "output"))
    )
    (net (code "92") (name "unconnected-(U2-GPIO2{slash}KBR3-Pad41)") (class "Default")
      (node (ref "U2") (pin "41") (pinfunction "GPIO2/KBR3_41") (pintype "output"))
    )
    (net (code "93") (name "unconnected-(U2-GPIO3{slash}KBR2-Pad42)") (class "Default")
      (node (ref "U2") (pin "42") (pinfunction "GPIO3/KBR2_42") (pintype "output"))
    )
    (net (code "94") (name "unconnected-(U2-GPIO4{slash}KBR1-Pad43)") (class "Default")
      (node (ref "U2") (pin "43") (pinfunction "GPIO4/KBR1_43") (pintype "output"))
    )
    (net (code "95") (name "unconnected-(U2-GPIO5{slash}KBR0-Pad44)") (class "Default")
      (node (ref "U2") (pin "44") (pinfunction "GPIO5/KBR0_44") (pintype "output"))
    )
    (net (code "96") (name "unconnected-(U2-GPIO6{slash}KBC4-Pad47)") (class "Default")
      (node (ref "U2") (pin "47") (pinfunction "GPIO6/KBC4_47") (pintype "input"))
    )
    (net (code "97") (name "unconnected-(U2-GPIO7{slash}KBC3-Pad48)") (class "Default")
      (node (ref "U2") (pin "48") (pinfunction "GPIO7/KBC3_48") (pintype "bidirectional"))
    )
    (net (code "98") (name "unconnected-(U2-GPIO8{slash}KBC2-Pad49)") (class "Default")
      (node (ref "U2") (pin "49") (pinfunction "GPIO8/KBC2_49") (pintype "input"))
    )
    (net (code "99") (name "unconnected-(U2-GPIO9{slash}KBC1-Pad50)") (class "Default")
      (node (ref "U2") (pin "50") (pinfunction "GPIO9/KBC1_50") (pintype "input"))
    )
    (net (code "100") (name "unconnected-(U2-GPIO10{slash}KBC0-Pad51)") (class "Default")
      (node (ref "U2") (pin "51") (pinfunction "GPIO10/KBC0_51") (pintype "bidirectional"))
    )
    (net (code "101") (name "unconnected-(U2-GPIO11-Pad67)") (class "Default")
      (node (ref "U2") (pin "67") (pinfunction "GPIO11_67") (pintype "bidirectional"))
    )
    (net (code "102") (name "unconnected-(U2-GPIO12-Pad68)") (class "Default")
      (node (ref "U2") (pin "68") (pinfunction "GPIO12_68") (pintype "bidirectional"))
    )
    (net (code "103") (name "unconnected-(U2-LINEIN_L-Pad24)") (class "Default")
      (node (ref "U2") (pin "24") (pinfunction "LINEIN_L_24") (pintype "input"))
    )
    (net (code "104") (name "unconnected-(U2-LINEIN_R-Pad23)") (class "Default")
      (node (ref "U2") (pin "23") (pinfunction "LINEIN_R_23") (pintype "input"))
    )
    (net (code "105") (name "unconnected-(U2-MIC_N-Pad20)") (class "Default")
      (node (ref "U2") (pin "20") (pinfunction "MIC_N_20") (pintype "input"))
    )
    (net (code "106") (name "unconnected-(U2-MIC_P-Pad19)") (class "Default")
      (node (ref "U2") (pin "19") (pinfunction "MIC_P_19") (pintype "input"))
    )
    (net (code "107") (name "unconnected-(U2-NETLIGHT-Pad52)") (class "Default")
      (node (ref "U2") (pin "52") (pinfunction "NETLIGHT_52") (pintype "output"))
    )
    (net (code "108") (name "unconnected-(U2-PWM1-Pad35)") (class "Default")
      (node (ref "U2") (pin "35") (pinfunction "PWM1_35") (pintype "output"))
    )
    (net (code "109") (name "unconnected-(U2-PWM2-Pad36)") (class "Default")
      (node (ref "U2") (pin "36") (pinfunction "PWM2_36") (pintype "output"))
    )
    (net (code "110") (name "unconnected-(U2-PWRKEY_OUT-Pad2)") (class "Default")
      (node (ref "U2") (pin "2") (pinfunction "PWRKEY_OUT_2") (pintype "output"))
    )
    (net (code "111") (name "unconnected-(U2-RI-Pad4)") (class "Default")
      (node (ref "U2") (pin "4") (pinfunction "RI_4") (pintype "output"))
    )
    (net (code "112") (name "unconnected-(U2-RTS-Pad8)") (class "Default")
      (node (ref "U2") (pin "8") (pinfunction "RTS_8") (pintype "input"))
    )
    (net (code "113") (name "unconnected-(U2-SCL-Pad38)") (class "Default")
      (node (ref "U2") (pin "38") (pinfunction "SCL_38") (pintype "output"))
    )
    (net (code "114") (name "unconnected-(U2-SDA-Pad37)") (class "Default")
      (node (ref "U2") (pin "37") (pinfunction "SDA_37") (pintype "bidirectional"))
    )
    (net (code "115") (name "unconnected-(U2-SIM_PRESENCE-Pad34)") (class "Default")
      (node (ref "U2") (pin "34") (pinfunction "SIM_PRESENCE_34") (pintype "input"))
    )
    (net (code "116") (name "unconnected-(U2-SPK_N-Pad22)") (class "Default")
      (node (ref "U2") (pin "22") (pinfunction "SPK_N_22") (pintype "output"))
    )
    (net (code "117") (name "unconnected-(U2-SPK_P-Pad21)") (class "Default")
      (node (ref "U2") (pin "21") (pinfunction "SPK_P_21") (pintype "output"))
    )
    (net (code "118") (name "unconnected-(U2-VDD_EXT-Pad15)") (class "Default")
      (node (ref "U2") (pin "15") (pinfunction "VDD_EXT_15") (pintype "output"))
    )
    (net (code "119") (name "unconnected-(U2-VRTC-Pad26)") (class "Default")
      (node (ref "U2") (pin "26") (pinfunction "VRTC_26") (pintype "bidirectional"))
    )
    (net (code "120") (name "unconnected-(X1-Pad2)") (class "Default")
      (node (ref "X1") (pin "2") (pinfunction "2_2") (pintype "passive"))
    )
    (net (code "121") (name "unconnected-(X1-Pad3)") (class "Default")
      (node (ref "X1") (pin "3") (pinfunction "3_3") (pintype "passive"))
    )
    (net (code "122") (name "unconnected-(X1-Pad4)") (class "Default")
      (node (ref "X1") (pin "4") (pinfunction "4_4") (pintype "passive"))
    )
  )
)
